# haccess-v1.net
KiCad netlist of a schematic drawn in EAGLE
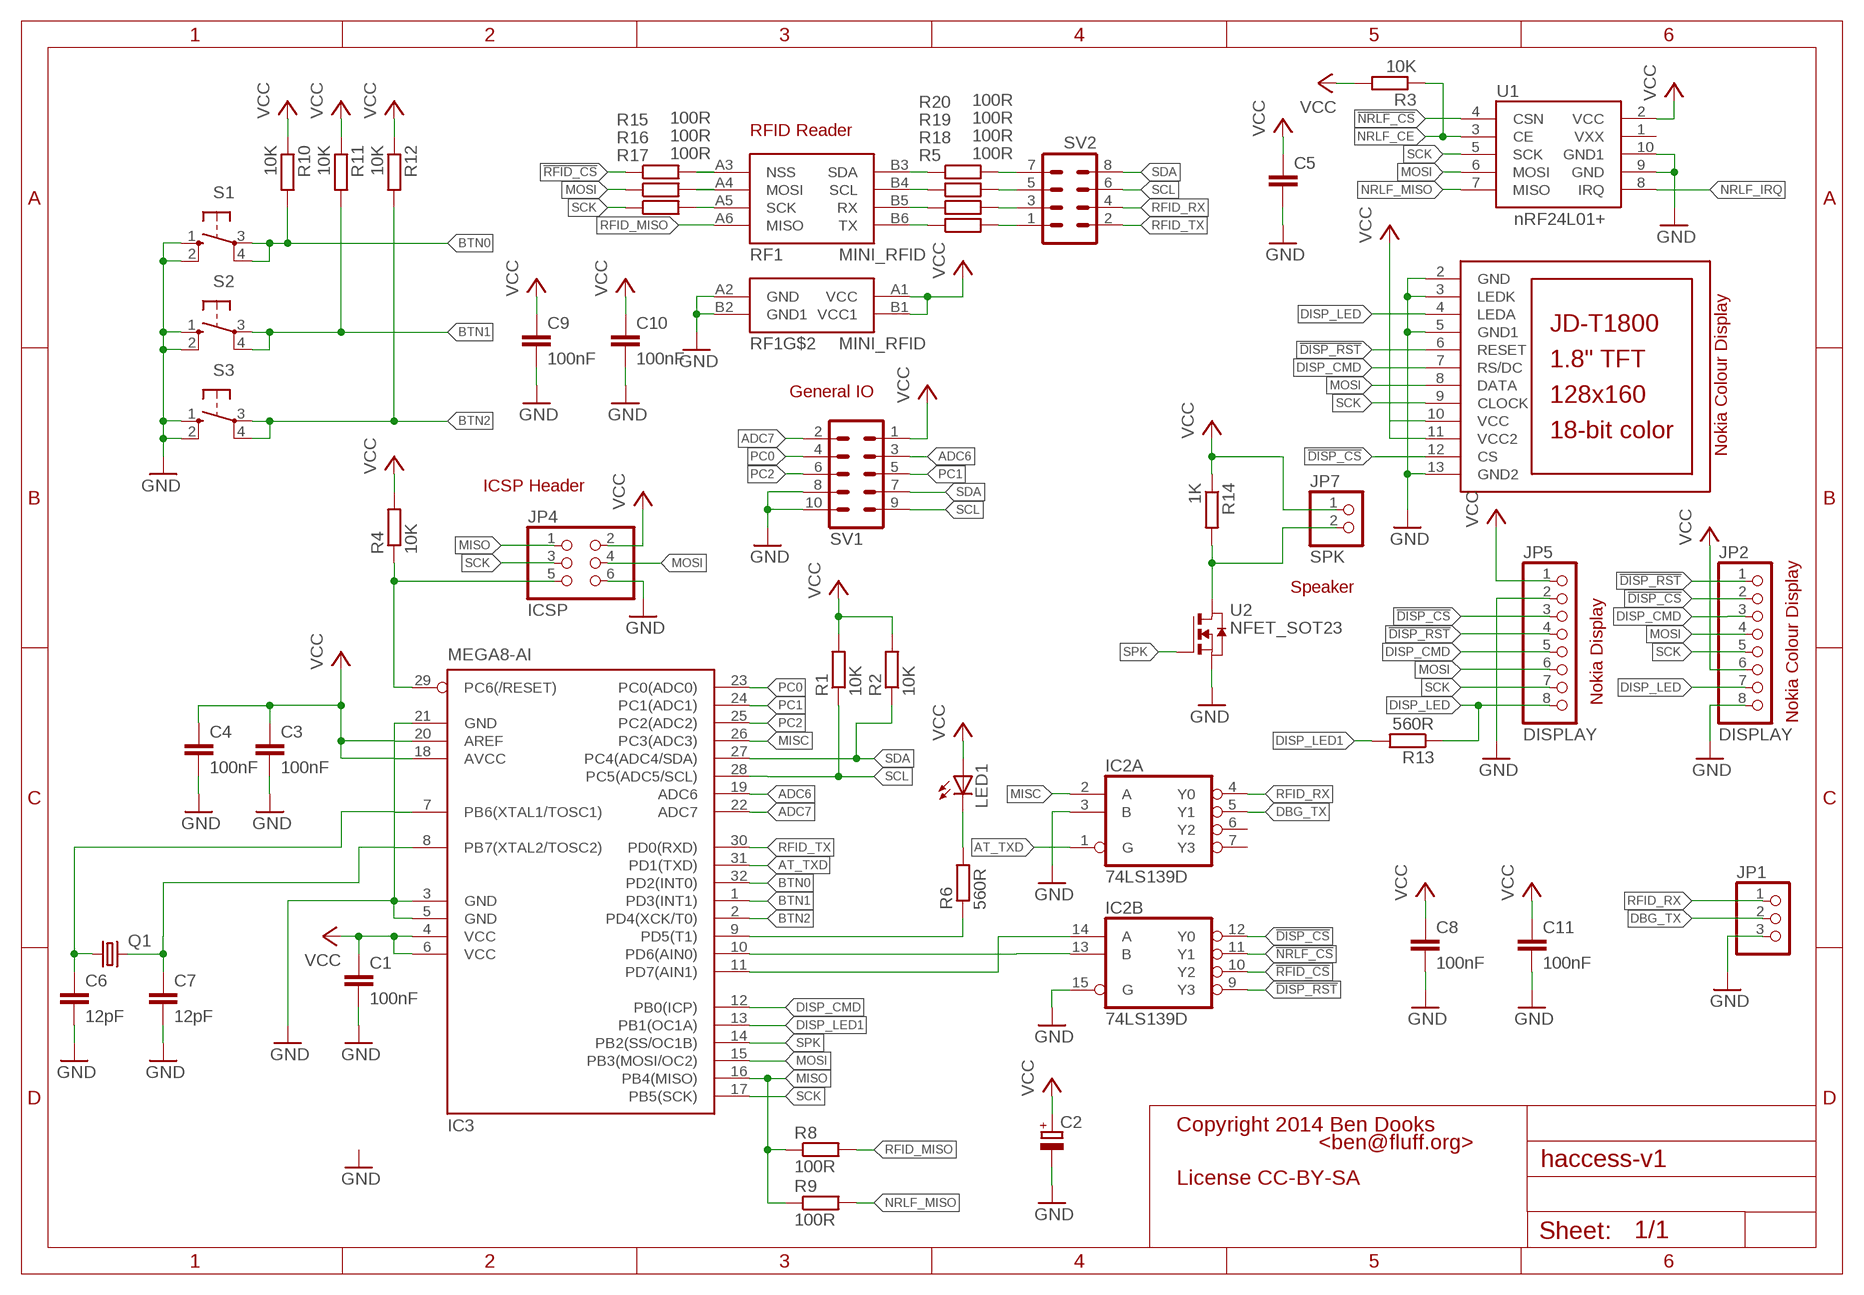
[diagram p0: schematic, sheet 1]

(export (version "E")
  (design (tool "Eeschema 10.0.6"))
  (components
    (comp (ref "C1")
      (value "100nF")
      (footprint "eagle-import:C025-030X050")
      (libsource (lib "eagle-import") (part "C-EU025-030X050"))
    )
    (comp (ref "C2")
      (value "CPOL-EUE2.5-6")
      (footprint "eagle-import:E2,5-6")
      (libsource (lib "eagle-import") (part "CPOL-EUE2.5-6"))
    )
    (comp (ref "C3")
      (value "100nF")
      (footprint "eagle-import:C0603K")
      (libsource (lib "eagle-import") (part "C-EUC0603K"))
    )
    (comp (ref "C4")
      (value "100nF")
      (footprint "eagle-import:C0603K")
      (libsource (lib "eagle-import") (part "C-EUC0603K"))
    )
    (comp (ref "C5")
      (value "C-EU025-030X050")
      (footprint "eagle-import:C025-030X050")
      (libsource (lib "eagle-import") (part "C-EU025-030X050"))
    )
    (comp (ref "C6")
      (value "12pF")
      (footprint "eagle-import:C0603K")
      (libsource (lib "eagle-import") (part "C-EUC0603K"))
    )
    (comp (ref "C7")
      (value "12pF")
      (footprint "eagle-import:C0603K")
      (libsource (lib "eagle-import") (part "C-EUC0603K"))
    )
    (comp (ref "C8")
      (value "100nF")
      (footprint "eagle-import:C0603K")
      (libsource (lib "eagle-import") (part "C-EUC0603K"))
    )
    (comp (ref "C9")
      (value "100nF")
      (footprint "eagle-import:C025-030X050")
      (libsource (lib "eagle-import") (part "C-EU025-030X050"))
    )
    (comp (ref "C10")
      (value "100nF")
      (footprint "eagle-import:C025-030X050")
      (libsource (lib "eagle-import") (part "C-EU025-030X050"))
    )
    (comp (ref "C11")
      (value "100nF")
      (footprint "eagle-import:C0603K")
      (libsource (lib "eagle-import") (part "C-EUC0603K"))
    )
    (comp (ref "IC2")
      (value "74LS139D")
      (footprint "eagle-import:SO16")
      (libsource (lib "eagle-import") (part "74139DLS"))
    )
    (comp (ref "IC3")
      (value "MEGA8-AI")
      (footprint "eagle-import:TQFP32-08")
      (fields (field (name "MPN") "ATMEGA8-16AU"))
      (libsource (lib "eagle-import") (part "MEGA8-AI"))
    )
    (comp (ref "JP1")
      (value "PINHD-1X3")
      (footprint "eagle-import:1X03")
      (libsource (lib "eagle-import") (part "PINHD-1X3"))
    )
    (comp (ref "JP2")
      (value "DISPLAY")
      (footprint "eagle-import:1X08")
      (libsource (lib "eagle-import") (part "PINHD-1X8"))
    )
    (comp (ref "JP4")
      (value "ICSP")
      (footprint "eagle-import:2X03")
      (libsource (lib "eagle-import") (part "PINHD-2X3"))
    )
    (comp (ref "JP5")
      (value "DISPLAY")
      (footprint "eagle-import:1X08")
      (libsource (lib "eagle-import") (part "PINHD-1X8"))
    )
    (comp (ref "JP7")
      (value "SPK")
      (footprint "eagle-import:1X02")
      (libsource (lib "eagle-import") (part "PINHD-1X2"))
    )
    (comp (ref "LCD1")
      (value "JD-T1800")
      (footprint "eagle-import:JD-T1800")
      (libsource (lib "eagle-import") (part "JD-T1800"))
    )
    (comp (ref "LED1")
      (value "LED5MM")
      (footprint "eagle-import:LED5MM")
      (libsource (lib "eagle-import") (part "LED5MM"))
    )
    (comp (ref "Q1")
      (value "CRYSTALHC49S")
      (footprint "eagle-import:HC49_S")
      (libsource (lib "eagle-import") (part "CRYSTALHC49S"))
    )
    (comp (ref "R1")
      (value "10K")
      (footprint "eagle-import:R0603")
      (libsource (lib "eagle-import") (part "R-EU_R0603"))
    )
    (comp (ref "R2")
      (value "10K")
      (footprint "eagle-import:R0603")
      (libsource (lib "eagle-import") (part "R-EU_R0603"))
    )
    (comp (ref "R3")
      (value "10K")
      (footprint "eagle-import:R0603")
      (libsource (lib "eagle-import") (part "R-EU_R0603"))
    )
    (comp (ref "R4")
      (value "10K")
      (footprint "eagle-import:R0603")
      (libsource (lib "eagle-import") (part "R-EU_R0603"))
    )
    (comp (ref "R5")
      (value "100R")
      (footprint "eagle-import:R0603")
      (libsource (lib "eagle-import") (part "R-EU_R0603"))
    )
    (comp (ref "R6")
      (value "560R")
      (footprint "eagle-import:R0603")
      (libsource (lib "eagle-import") (part "R-EU_R0603"))
    )
    (comp (ref "R8")
      (value "100R")
      (footprint "eagle-import:0204_7")
      (libsource (lib "eagle-import") (part "R-EU_0204/7"))
    )
    (comp (ref "R9")
      (value "100R")
      (footprint "eagle-import:0204_7")
      (libsource (lib "eagle-import") (part "R-EU_0204/7"))
    )
    (comp (ref "R10")
      (value "10K")
      (footprint "eagle-import:R0603")
      (libsource (lib "eagle-import") (part "R-EU_R0603"))
    )
    (comp (ref "R11")
      (value "10K")
      (footprint "eagle-import:R0603")
      (libsource (lib "eagle-import") (part "R-EU_R0603"))
    )
    (comp (ref "R12")
      (value "10K")
      (footprint "eagle-import:R0603")
      (libsource (lib "eagle-import") (part "R-EU_R0603"))
    )
    (comp (ref "R13")
      (value "560R")
      (footprint "eagle-import:0204_7")
      (libsource (lib "eagle-import") (part "R-EU_0204/7"))
    )
    (comp (ref "R14")
      (value "1K")
      (footprint "eagle-import:R0603")
      (libsource (lib "eagle-import") (part "R-EU_R0603"))
    )
    (comp (ref "R15")
      (value "100R")
      (footprint "eagle-import:0207_10")
      (libsource (lib "eagle-import") (part "R-EU_0207/10"))
    )
    (comp (ref "R16")
      (value "100R")
      (footprint "eagle-import:0207_10")
      (libsource (lib "eagle-import") (part "R-EU_0207/10"))
    )
    (comp (ref "R17")
      (value "100R")
      (footprint "eagle-import:0207_7")
      (libsource (lib "eagle-import") (part "R-EU_0207/7"))
    )
    (comp (ref "R18")
      (value "100R")
      (footprint "eagle-import:R0603")
      (libsource (lib "eagle-import") (part "R-EU_R0603"))
    )
    (comp (ref "R19")
      (value "100R")
      (footprint "eagle-import:R0603")
      (libsource (lib "eagle-import") (part "R-EU_R0603"))
    )
    (comp (ref "R20")
      (value "100R")
      (footprint "eagle-import:R0603")
      (libsource (lib "eagle-import") (part "R-EU_R0603"))
    )
    (comp (ref "RF1")
      (value "MINI_RFID")
      (footprint "eagle-import:MINI_RFID")
      (libsource (lib "eagle-import") (part "MINI_RFID"))
    )
    (comp (ref "S1")
      (value "10-XX")
      (footprint "eagle-import:B3F-10XX")
      (fields (field (name "MPN") "B3F-1000"))
      (libsource (lib "eagle-import") (part "10-XX"))
    )
    (comp (ref "S2")
      (value "10-XX")
      (footprint "eagle-import:B3F-10XX")
      (fields (field (name "MPN") "B3F-1000"))
      (libsource (lib "eagle-import") (part "10-XX"))
    )
    (comp (ref "S3")
      (value "10-XX")
      (footprint "eagle-import:B3F-10XX")
      (fields (field (name "MPN") "B3F-1000"))
      (libsource (lib "eagle-import") (part "10-XX"))
    )
    (comp (ref "SV1")
      (value "MA05-2")
      (footprint "eagle-import:MA05-2")
      (libsource (lib "eagle-import") (part "MA05-2"))
    )
    (comp (ref "SV2")
      (value "MA04-2")
      (footprint "eagle-import:MA04-2")
      (libsource (lib "eagle-import") (part "MA04-2"))
    )
    (comp (ref "U1")
      (value "NRF24L01+CHINESE-10PIN")
      (footprint "eagle-import:CHINESE-10PIN")
      (libsource (lib "eagle-import") (part "NRF24L01+CHINESE-10PIN"))
    )
    (comp (ref "U2")
      (value "NFET_SOT23")
      (footprint "eagle-import:SOT23")
      (libsource (lib "eagle-import") (part "NFET_SOT23"))
    )
  )
  (nets
    (net (code "1") (name "/~{DISP_CS}") (class "Default")
      (node (ref "IC2") (pin "12") (pinfunction "Y0_12") (pintype "output"))
      (node (ref "JP2") (pin "2") (pinfunction "2_2") (pintype "passive"))
      (node (ref "JP5") (pin "3") (pinfunction "3_3") (pintype "passive"))
      (node (ref "LCD1") (pin "12") (pinfunction "CS_12") (pintype "input"))
    )
    (net (code "2") (name "/~{DISP_RST}") (class "Default")
      (node (ref "IC2") (pin "9") (pinfunction "Y3_9") (pintype "output"))
      (node (ref "JP2") (pin "1") (pinfunction "1_1") (pintype "passive"))
      (node (ref "JP5") (pin "4") (pinfunction "4_4") (pintype "passive"))
      (node (ref "LCD1") (pin "6") (pinfunction "RESET_6") (pintype "input"))
    )
    (net (code "3") (name "/~{NRLF_CS}") (class "Default")
      (node (ref "IC2") (pin "11") (pinfunction "Y1_11") (pintype "output"))
      (node (ref "U1") (pin "4") (pinfunction "CSN_4") (pintype "bidirectional"))
    )
    (net (code "4") (name "/~{RFID_CS}") (class "Default")
      (node (ref "IC2") (pin "10") (pinfunction "Y2_10") (pintype "output"))
      (node (ref "R15") (pin "1") (pinfunction "1_1") (pintype "passive"))
    )
    (net (code "5") (name "ADC6") (class "Default")
      (node (ref "IC3") (pin "19") (pinfunction "ADC6_19") (pintype "bidirectional"))
      (node (ref "SV1") (pin "3") (pinfunction "3_3") (pintype "passive"))
    )
    (net (code "6") (name "ADC7") (class "Default")
      (node (ref "IC3") (pin "22") (pinfunction "ADC7_22") (pintype "bidirectional"))
      (node (ref "SV1") (pin "2") (pinfunction "2_2") (pintype "passive"))
    )
    (net (code "7") (name "AT_TXD") (class "Default")
      (node (ref "IC2") (pin "1") (pinfunction "G_1") (pintype "input"))
      (node (ref "IC3") (pin "31") (pinfunction "PD1(TXD)_31") (pintype "bidirectional"))
    )
    (net (code "8") (name "BTN0") (class "Default")
      (node (ref "IC3") (pin "32") (pinfunction "PD2(INT0)_32") (pintype "bidirectional"))
      (node (ref "R10") (pin "2") (pinfunction "2_2") (pintype "passive"))
      (node (ref "S1") (pin "3") (pinfunction "P_3") (pintype "passive"))
      (node (ref "S1") (pin "4") (pinfunction "P1_4") (pintype "passive"))
    )
    (net (code "9") (name "BTN1") (class "Default")
      (node (ref "IC3") (pin "1") (pinfunction "PD3(INT1)_1") (pintype "bidirectional"))
      (node (ref "R11") (pin "2") (pinfunction "2_2") (pintype "passive"))
      (node (ref "S2") (pin "3") (pinfunction "P_3") (pintype "passive"))
      (node (ref "S2") (pin "4") (pinfunction "P1_4") (pintype "passive"))
    )
    (net (code "10") (name "BTN2") (class "Default")
      (node (ref "IC3") (pin "2") (pinfunction "PD4(XCK/T0)_2") (pintype "bidirectional"))
      (node (ref "R12") (pin "2") (pinfunction "2_2") (pintype "passive"))
      (node (ref "S3") (pin "3") (pinfunction "P_3") (pintype "passive"))
      (node (ref "S3") (pin "4") (pinfunction "P1_4") (pintype "passive"))
    )
    (net (code "11") (name "DBG_TX") (class "Default")
      (node (ref "IC2") (pin "5") (pinfunction "Y1_5") (pintype "output"))
      (node (ref "JP1") (pin "2") (pinfunction "2_2") (pintype "passive"))
    )
    (net (code "12") (name "DISP_CMD") (class "Default")
      (node (ref "IC3") (pin "12") (pinfunction "PB0(ICP)_12") (pintype "bidirectional"))
      (node (ref "JP2") (pin "3") (pinfunction "3_3") (pintype "passive"))
      (node (ref "JP5") (pin "5") (pinfunction "5_5") (pintype "passive"))
      (node (ref "LCD1") (pin "7") (pinfunction "RS/DC_7") (pintype "input"))
    )
    (net (code "13") (name "DISP_LED") (class "Default")
      (node (ref "JP2") (pin "7") (pinfunction "7_7") (pintype "passive"))
      (node (ref "JP5") (pin "8") (pinfunction "8_8") (pintype "passive"))
      (node (ref "LCD1") (pin "4") (pinfunction "LEDA_4") (pintype "input"))
      (node (ref "R13") (pin "1") (pinfunction "1_1") (pintype "passive"))
    )
    (net (code "14") (name "DISP_LED1") (class "Default")
      (node (ref "IC3") (pin "13") (pinfunction "PB1(OC1A)_13") (pintype "bidirectional"))
      (node (ref "R13") (pin "2") (pinfunction "2_2") (pintype "passive"))
    )
    (net (code "15") (name "GND") (class "Default")
      (node (ref "C1") (pin "2") (pinfunction "2_2") (pintype "passive"))
      (node (ref "C10") (pin "2") (pinfunction "2_2") (pintype "passive"))
      (node (ref "C11") (pin "2") (pinfunction "2_2") (pintype "passive"))
      (node (ref "C2") (pin "-") (pinfunction "-_-") (pintype "passive"))
      (node (ref "C3") (pin "2") (pinfunction "2_2") (pintype "passive"))
      (node (ref "C4") (pin "2") (pinfunction "2_2") (pintype "passive"))
      (node (ref "C5") (pin "2") (pinfunction "2_2") (pintype "passive"))
      (node (ref "C6") (pin "2") (pinfunction "2_2") (pintype "passive"))
      (node (ref "C7") (pin "2") (pinfunction "2_2") (pintype "passive"))
      (node (ref "C8") (pin "2") (pinfunction "2_2") (pintype "passive"))
      (node (ref "C9") (pin "2") (pinfunction "2_2") (pintype "passive"))
      (node (ref "IC2") (pin "15") (pinfunction "G_15") (pintype "input"))
      (node (ref "IC2") (pin "3") (pinfunction "B_3") (pintype "input"))
      (node (ref "IC3") (pin "21") (pinfunction "GND_21") (pintype "power_in"))
      (node (ref "IC3") (pin "3") (pinfunction "GND_3") (pintype "power_in"))
      (node (ref "IC3") (pin "5") (pinfunction "GND_5") (pintype "power_in"))
      (node (ref "JP1") (pin "3") (pinfunction "3_3") (pintype "passive"))
      (node (ref "JP2") (pin "8") (pinfunction "8_8") (pintype "passive"))
      (node (ref "JP4") (pin "6") (pinfunction "6_6") (pintype "passive"))
      (node (ref "JP5") (pin "2") (pinfunction "2_2") (pintype "passive"))
      (node (ref "LCD1") (pin "13") (pinfunction "GND2_13") (pintype "power_in"))
      (node (ref "LCD1") (pin "2") (pinfunction "GND_2") (pintype "power_in"))
      (node (ref "LCD1") (pin "3") (pinfunction "LEDK_3") (pintype "input"))
      (node (ref "LCD1") (pin "5") (pinfunction "GND1_5") (pintype "power_in"))
      (node (ref "RF1") (pin "A2") (pinfunction "GND_A2") (pintype "power_in"))
      (node (ref "RF1") (pin "B2") (pinfunction "GND1_B2") (pintype "power_in"))
      (node (ref "S1") (pin "1") (pinfunction "S_1") (pintype "passive"))
      (node (ref "S1") (pin "2") (pinfunction "S1_2") (pintype "passive"))
      (node (ref "S2") (pin "1") (pinfunction "S_1") (pintype "passive"))
      (node (ref "S2") (pin "2") (pinfunction "S1_2") (pintype "passive"))
      (node (ref "S3") (pin "1") (pinfunction "S_1") (pintype "passive"))
      (node (ref "S3") (pin "2") (pinfunction "S1_2") (pintype "passive"))
      (node (ref "SV1") (pin "10") (pinfunction "10_10") (pintype "passive"))
      (node (ref "SV1") (pin "8") (pinfunction "8_8") (pintype "passive"))
      (node (ref "U1") (pin "10") (pinfunction "GND1_10") (pintype "bidirectional"))
      (node (ref "U1") (pin "9") (pinfunction "GND_9") (pintype "bidirectional"))
      (node (ref "U2") (pin "2") (pinfunction "S_2") (pintype "passive"))
    )
    (net (code "16") (name "MISC") (class "Default")
      (node (ref "IC2") (pin "2") (pinfunction "A_2") (pintype "input"))
      (node (ref "IC3") (pin "26") (pinfunction "PC3(ADC3)_26") (pintype "bidirectional"))
    )
    (net (code "17") (name "MISO") (class "Default")
      (node (ref "IC3") (pin "16") (pinfunction "PB4(MISO)_16") (pintype "bidirectional"))
      (node (ref "JP4") (pin "1") (pinfunction "1_1") (pintype "passive"))
      (node (ref "R8") (pin "1") (pinfunction "1_1") (pintype "passive"))
      (node (ref "R9") (pin "1") (pinfunction "1_1") (pintype "passive"))
    )
    (net (code "18") (name "MOSI") (class "Default")
      (node (ref "IC3") (pin "15") (pinfunction "PB3(MOSI/OC2)_15") (pintype "bidirectional"))
      (node (ref "JP2") (pin "4") (pinfunction "4_4") (pintype "passive"))
      (node (ref "JP4") (pin "4") (pinfunction "4_4") (pintype "passive"))
      (node (ref "JP5") (pin "6") (pinfunction "6_6") (pintype "passive"))
      (node (ref "LCD1") (pin "8") (pinfunction "DATA_8") (pintype "bidirectional"))
      (node (ref "R16") (pin "1") (pinfunction "1_1") (pintype "passive"))
      (node (ref "U1") (pin "6") (pinfunction "MOSI_6") (pintype "bidirectional"))
    )
    (net (code "19") (name "NRLF_CE") (class "Default")
      (node (ref "R3") (pin "1") (pinfunction "1_1") (pintype "passive"))
      (node (ref "U1") (pin "3") (pinfunction "CE_3") (pintype "bidirectional"))
    )
    (net (code "20") (name "NRLF_IRQ") (class "Default")
      (node (ref "U1") (pin "8") (pinfunction "IRQ_8") (pintype "bidirectional"))
    )
    (net (code "21") (name "NRLF_MISO") (class "Default")
      (node (ref "R9") (pin "2") (pinfunction "2_2") (pintype "passive"))
      (node (ref "U1") (pin "7") (pinfunction "MISO_7") (pintype "bidirectional"))
    )
    (net (code "22") (name "Net-(IC2B-A)") (class "Default")
      (node (ref "IC2") (pin "14") (pinfunction "A_14") (pintype "input"))
      (node (ref "IC3") (pin "11") (pinfunction "PD7(AIN1)_11") (pintype "bidirectional"))
    )
    (net (code "23") (name "Net-(IC2B-B)") (class "Default")
      (node (ref "IC2") (pin "13") (pinfunction "B_13") (pintype "input"))
      (node (ref "IC3") (pin "10") (pinfunction "PD6(AIN0)_10") (pintype "bidirectional"))
    )
    (net (code "24") (name "Net-(IC3-PB6(XTAL1{slash}TOSC1))") (class "Default")
      (node (ref "C6") (pin "1") (pinfunction "1_1") (pintype "passive"))
      (node (ref "IC3") (pin "7") (pinfunction "PB6(XTAL1/TOSC1)_7") (pintype "bidirectional"))
      (node (ref "Q1") (pin "1") (pinfunction "1_1") (pintype "passive"))
    )
    (net (code "25") (name "Net-(IC3-PB7(XTAL2{slash}TOSC2))") (class "Default")
      (node (ref "C7") (pin "1") (pinfunction "1_1") (pintype "passive"))
      (node (ref "IC3") (pin "8") (pinfunction "PB7(XTAL2/TOSC2)_8") (pintype "bidirectional"))
      (node (ref "Q1") (pin "2") (pinfunction "2_2") (pintype "passive"))
    )
    (net (code "26") (name "Net-(IC3-PC6({slash}RESET))") (class "Default")
      (node (ref "IC3") (pin "29") (pinfunction "PC6(/RESET)_29") (pintype "bidirectional"))
      (node (ref "JP4") (pin "5") (pinfunction "5_5") (pintype "passive"))
      (node (ref "R4") (pin "1") (pinfunction "1_1") (pintype "passive"))
    )
    (net (code "27") (name "Net-(IC3-PD5(T1))") (class "Default")
      (node (ref "IC3") (pin "9") (pinfunction "PD5(T1)_9") (pintype "bidirectional"))
      (node (ref "R6") (pin "1") (pinfunction "1_1") (pintype "passive"))
    )
    (net (code "28") (name "Net-(LED1-C)") (class "Default")
      (node (ref "LED1") (pin "K") (pinfunction "C_K") (pintype "passive"))
      (node (ref "R6") (pin "2") (pinfunction "2_2") (pintype "passive"))
    )
    (net (code "29") (name "Net-(R5-Pad2)") (class "Default")
      (node (ref "R5") (pin "2") (pinfunction "2_2") (pintype "passive"))
      (node (ref "SV2") (pin "1") (pinfunction "1_1") (pintype "passive"))
    )
    (net (code "30") (name "Net-(R18-Pad2)") (class "Default")
      (node (ref "R18") (pin "2") (pinfunction "2_2") (pintype "passive"))
      (node (ref "SV2") (pin "3") (pinfunction "3_3") (pintype "passive"))
    )
    (net (code "31") (name "Net-(R19-Pad2)") (class "Default")
      (node (ref "R19") (pin "2") (pinfunction "2_2") (pintype "passive"))
      (node (ref "SV2") (pin "5") (pinfunction "5_5") (pintype "passive"))
    )
    (net (code "32") (name "Net-(R20-Pad2)") (class "Default")
      (node (ref "R20") (pin "2") (pinfunction "2_2") (pintype "passive"))
      (node (ref "SV2") (pin "7") (pinfunction "7_7") (pintype "passive"))
    )
    (net (code "33") (name "Net-(RF1A-MOSI)") (class "Default")
      (node (ref "R16") (pin "2") (pinfunction "2_2") (pintype "passive"))
      (node (ref "RF1") (pin "A4") (pinfunction "MOSI_A4") (pintype "bidirectional"))
    )
    (net (code "34") (name "Net-(RF1A-NSS)") (class "Default")
      (node (ref "R15") (pin "2") (pinfunction "2_2") (pintype "passive"))
      (node (ref "RF1") (pin "A3") (pinfunction "NSS_A3") (pintype "bidirectional"))
    )
    (net (code "35") (name "Net-(RF1A-RX)") (class "Default")
      (node (ref "R18") (pin "1") (pinfunction "1_1") (pintype "passive"))
      (node (ref "RF1") (pin "B5") (pinfunction "RX_B5") (pintype "bidirectional"))
    )
    (net (code "36") (name "Net-(RF1A-SCK)") (class "Default")
      (node (ref "R17") (pin "2") (pinfunction "2_2") (pintype "passive"))
      (node (ref "RF1") (pin "A5") (pinfunction "SCK_A5") (pintype "bidirectional"))
    )
    (net (code "37") (name "Net-(RF1A-SCL)") (class "Default")
      (node (ref "R19") (pin "1") (pinfunction "1_1") (pintype "passive"))
      (node (ref "RF1") (pin "B4") (pinfunction "SCL_B4") (pintype "bidirectional"))
    )
    (net (code "38") (name "Net-(RF1A-SDA)") (class "Default")
      (node (ref "R20") (pin "1") (pinfunction "1_1") (pintype "passive"))
      (node (ref "RF1") (pin "B3") (pinfunction "SDA_B3") (pintype "bidirectional"))
    )
    (net (code "39") (name "Net-(RF1A-TX)") (class "Default")
      (node (ref "R5") (pin "1") (pinfunction "1_1") (pintype "passive"))
      (node (ref "RF1") (pin "B6") (pinfunction "TX_B6") (pintype "bidirectional"))
    )
    (net (code "40") (name "Net-(U2-D)") (class "Default")
      (node (ref "JP7") (pin "2") (pinfunction "2_2") (pintype "passive"))
      (node (ref "R14") (pin "2") (pinfunction "2_2") (pintype "passive"))
      (node (ref "U2") (pin "3") (pinfunction "D_3") (pintype "passive"))
    )
    (net (code "41") (name "PC0") (class "Default")
      (node (ref "IC3") (pin "23") (pinfunction "PC0(ADC0)_23") (pintype "bidirectional"))
      (node (ref "SV1") (pin "4") (pinfunction "4_4") (pintype "passive"))
    )
    (net (code "42") (name "PC1") (class "Default")
      (node (ref "IC3") (pin "24") (pinfunction "PC1(ADC1)_24") (pintype "bidirectional"))
      (node (ref "SV1") (pin "5") (pinfunction "5_5") (pintype "passive"))
    )
    (net (code "43") (name "PC2") (class "Default")
      (node (ref "IC3") (pin "25") (pinfunction "PC2(ADC2)_25") (pintype "bidirectional"))
      (node (ref "SV1") (pin "6") (pinfunction "6_6") (pintype "passive"))
    )
    (net (code "44") (name "RFID_MISO") (class "Default")
      (node (ref "R8") (pin "2") (pinfunction "2_2") (pintype "passive"))
      (node (ref "RF1") (pin "A6") (pinfunction "MISO_A6") (pintype "bidirectional"))
    )
    (net (code "45") (name "RFID_RX") (class "Default")
      (node (ref "IC2") (pin "4") (pinfunction "Y0_4") (pintype "output"))
      (node (ref "JP1") (pin "1") (pinfunction "1_1") (pintype "passive"))
      (node (ref "SV2") (pin "4") (pinfunction "4_4") (pintype "passive"))
    )
    (net (code "46") (name "RFID_TX") (class "Default")
      (node (ref "IC3") (pin "30") (pinfunction "PD0(RXD)_30") (pintype "bidirectional"))
      (node (ref "SV2") (pin "2") (pinfunction "2_2") (pintype "passive"))
    )
    (net (code "47") (name "SCK") (class "Default")
      (node (ref "IC3") (pin "17") (pinfunction "PB5(SCK)_17") (pintype "bidirectional"))
      (node (ref "JP2") (pin "5") (pinfunction "5_5") (pintype "passive"))
      (node (ref "JP4") (pin "3") (pinfunction "3_3") (pintype "passive"))
      (node (ref "JP5") (pin "7") (pinfunction "7_7") (pintype "passive"))
      (node (ref "LCD1") (pin "9") (pinfunction "CLOCK_9") (pintype "input"))
      (node (ref "R17") (pin "1") (pinfunction "1_1") (pintype "passive"))
      (node (ref "U1") (pin "5") (pinfunction "SCK_5") (pintype "bidirectional"))
    )
    (net (code "48") (name "SCL") (class "Default")
      (node (ref "IC3") (pin "28") (pinfunction "PC5(ADC5/SCL)_28") (pintype "bidirectional"))
      (node (ref "R1") (pin "1") (pinfunction "1_1") (pintype "passive"))
      (node (ref "SV1") (pin "9") (pinfunction "9_9") (pintype "passive"))
      (node (ref "SV2") (pin "6") (pinfunction "6_6") (pintype "passive"))
    )
    (net (code "49") (name "SDA") (class "Default")
      (node (ref "IC3") (pin "27") (pinfunction "PC4(ADC4/SDA)_27") (pintype "bidirectional"))
      (node (ref "R2") (pin "1") (pinfunction "1_1") (pintype "passive"))
      (node (ref "SV1") (pin "7") (pinfunction "7_7") (pintype "passive"))
      (node (ref "SV2") (pin "8") (pinfunction "8_8") (pintype "passive"))
    )
    (net (code "50") (name "SPK") (class "Default")
      (node (ref "IC3") (pin "14") (pinfunction "PB2(SS/OC1B)_14") (pintype "bidirectional"))
      (node (ref "U2") (pin "1") (pinfunction "G_1") (pintype "passive"))
    )
    (net (code "51") (name "VCC") (class "Default")
      (node (ref "C1") (pin "1") (pinfunction "1_1") (pintype "passive"))
      (node (ref "C10") (pin "1") (pinfunction "1_1") (pintype "passive"))
      (node (ref "C11") (pin "1") (pinfunction "1_1") (pintype "passive"))
      (node (ref "C2") (pin "+") (pinfunction "+_+") (pintype "passive"))
      (node (ref "C3") (pin "1") (pinfunction "1_1") (pintype "passive"))
      (node (ref "C4") (pin "1") (pinfunction "1_1") (pintype "passive"))
      (node (ref "C5") (pin "1") (pinfunction "1_1") (pintype "passive"))
      (node (ref "C8") (pin "1") (pinfunction "1_1") (pintype "passive"))
      (node (ref "C9") (pin "1") (pinfunction "1_1") (pintype "passive"))
      (node (ref "IC3") (pin "18") (pinfunction "AVCC_18") (pintype "power_in"))
      (node (ref "IC3") (pin "20") (pinfunction "AREF_20") (pintype "passive"))
      (node (ref "IC3") (pin "4") (pinfunction "VCC_4") (pintype "power_in"))
      (node (ref "IC3") (pin "6") (pinfunction "VCC_6") (pintype "power_in"))
      (node (ref "JP2") (pin "6") (pinfunction "6_6") (pintype "passive"))
      (node (ref "JP4") (pin "2") (pinfunction "2_2") (pintype "passive"))
      (node (ref "JP5") (pin "1") (pinfunction "1_1") (pintype "passive"))
      (node (ref "JP7") (pin "1") (pinfunction "1_1") (pintype "passive"))
      (node (ref "LCD1") (pin "10") (pinfunction "VCC_10") (pintype "power_in"))
      (node (ref "LCD1") (pin "11") (pinfunction "VCC2_11") (pintype "power_in"))
      (node (ref "LED1") (pin "A") (pinfunction "A_A") (pintype "passive"))
      (node (ref "R1") (pin "2") (pinfunction "2_2") (pintype "passive"))
      (node (ref "R10") (pin "1") (pinfunction "1_1") (pintype "passive"))
      (node (ref "R11") (pin "1") (pinfunction "1_1") (pintype "passive"))
      (node (ref "R12") (pin "1") (pinfunction "1_1") (pintype "passive"))
      (node (ref "R14") (pin "1") (pinfunction "1_1") (pintype "passive"))
      (node (ref "R2") (pin "2") (pinfunction "2_2") (pintype "passive"))
      (node (ref "R3") (pin "2") (pinfunction "2_2") (pintype "passive"))
      (node (ref "R4") (pin "2") (pinfunction "2_2") (pintype "passive"))
      (node (ref "RF1") (pin "A1") (pinfunction "VCC_A1") (pintype "power_in"))
      (node (ref "RF1") (pin "B1") (pinfunction "VCC1_B1") (pintype "power_in"))
      (node (ref "SV1") (pin "1") (pinfunction "1_1") (pintype "passive"))
      (node (ref "U1") (pin "2") (pinfunction "VCC_2") (pintype "bidirectional"))
    )
    (net (code "52") (name "unconnected-(IC2A-Y2-Pad6)") (class "Default")
      (node (ref "IC2") (pin "6") (pinfunction "Y2_6") (pintype "output"))
    )
    (net (code "53") (name "unconnected-(IC2A-Y3-Pad7)") (class "Default")
      (node (ref "IC2") (pin "7") (pinfunction "Y3_7") (pintype "output"))
    )
    (net (code "54") (name "unconnected-(U1-VXX-Pad1)") (class "Default")
      (node (ref "U1") (pin "1") (pinfunction "VXX_1") (pintype "bidirectional"))
    )
  )
)
